# ProProject_board1_2023-08-19.net
KiCad netlist of a schematic drawn in EasyEDA Pro
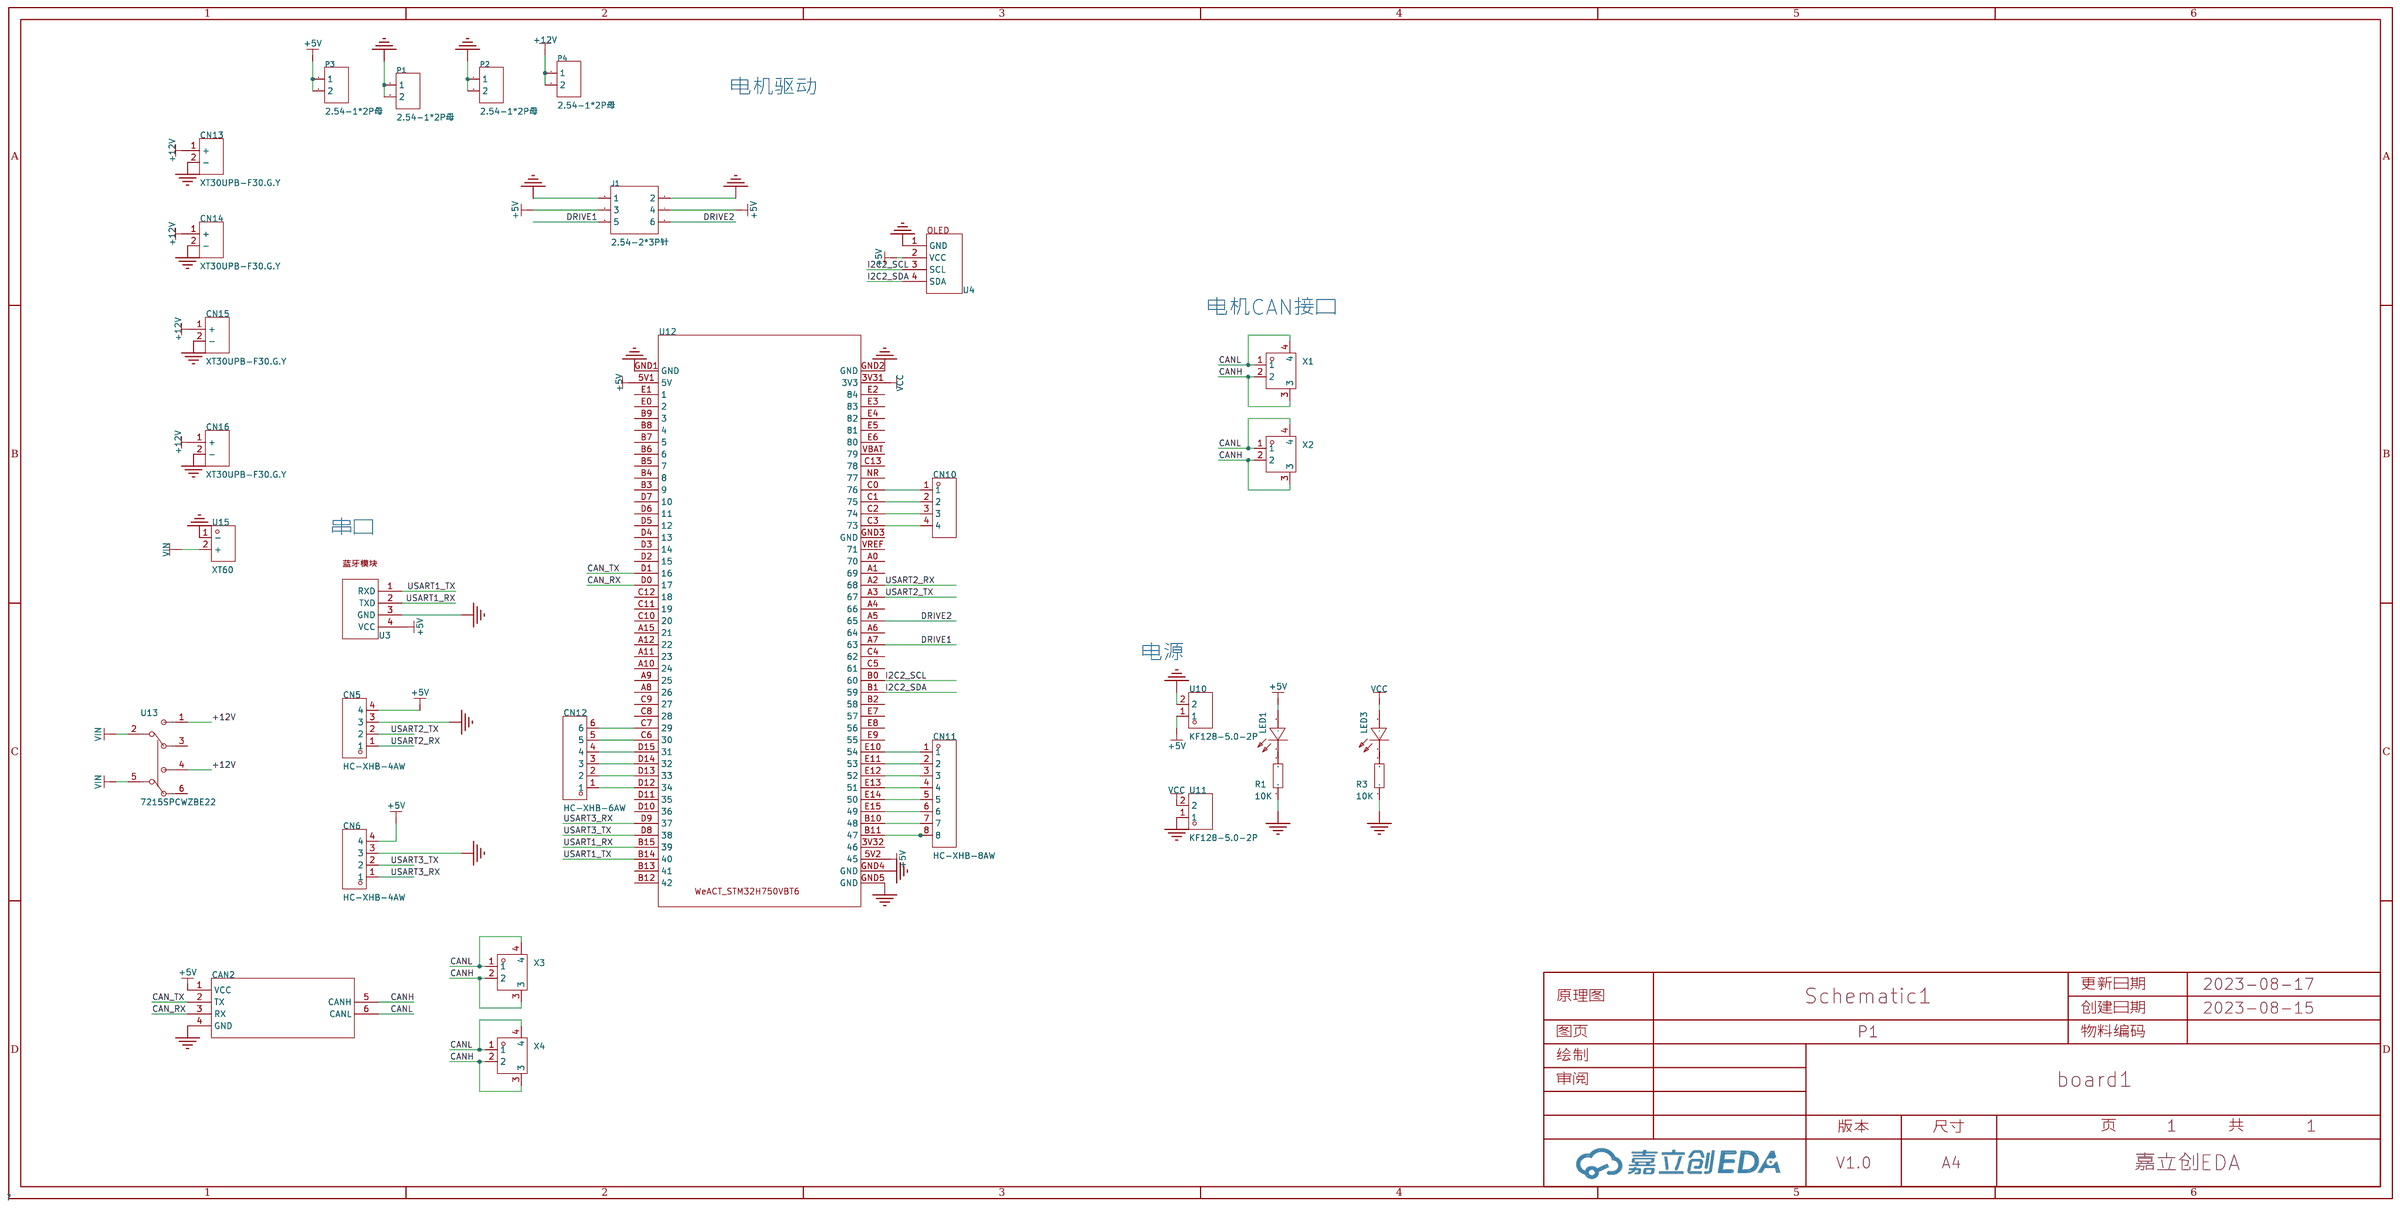
[diagram p0: schematic sheet]

(export (version "E")
  (design (tool "Eeschema 10.0.6"))
  (components
    (comp (ref "CAN2")
      (value "~")
      (footprint "easyedapro:CAN模块")
      (libsource (lib "easyedapro") (part "CAN模块"))
    )
    (comp (ref "CN5")
      (value "HC-XHB-4AW")
      (footprint "easyedapro:CONN-TH_4P-P2.5_HCTL_HC-XHB-4AW")
      (description "参考系列:-;间距:2.5mm;插针结构:1x4P;排数:1;每排PIN数:4;行距:-;公母:公型插针;安装方式:弯插;额定电流:3A;工作温度范围:-25°C~+85°C;")
      (fields (field (name "Manufacturer") "HCTL(华灿天禄)"))
      (libsource (lib "easyedapro") (part "HC-XHB-4AW"))
    )
    (comp (ref "CN6")
      (value "HC-XHB-4AW")
      (footprint "easyedapro:CONN-TH_4P-P2.5_HCTL_HC-XHB-4AW")
      (description "参考系列:-;间距:2.5mm;插针结构:1x4P;排数:1;每排PIN数:4;行距:-;公母:公型插针;安装方式:弯插;额定电流:3A;工作温度范围:-25°C~+85°C;")
      (fields (field (name "Manufacturer") "HCTL(华灿天禄)"))
      (libsource (lib "easyedapro") (part "HC-XHB-4AW"))
    )
    (comp (ref "CN10")
      (value "HC-XHB-4AW")
      (footprint "easyedapro:CONN-TH_4P-P2.5_HCTL_HC-XHB-4AW")
      (description "参考系列:-;间距:2.5mm;插针结构:1x4P;排数:1;每排PIN数:4;行距:-;公母:公型插针;安装方式:弯插;额定电流:3A;工作温度范围:-25°C~+85°C;")
      (fields (field (name "Manufacturer") "HCTL(华灿天禄)"))
      (libsource (lib "easyedapro") (part "HC-XHB-4AW"))
    )
    (comp (ref "CN11")
      (value "HC-XHB-8AW")
      (footprint "easyedapro:CONN-TH_HC-XHB-8AW")
      (description "参考系列:-;间距:2.5mm;插针结构:1x8P;排数:1;每排PIN数:8;行距:-;公母:公型插针;安装方式:弯插;额定电流:3A;工作温度范围:-25°C~+85°C;")
      (fields (field (name "Manufacturer") "HCTL(华灿天禄)"))
      (libsource (lib "easyedapro") (part "HC-XHB-8AW"))
    )
    (comp (ref "CN12")
      (value "HC-XHB-6AW")
      (footprint "easyedapro:CONN-TH_6P-P2.50_HCTL_HC-XHB-6AW")
      (description "参考系列:-;间距:2.5mm;插针结构:1x6P;排数:1;每排PIN数:6;行距:-;公母:公型插针;安装方式:弯插;额定电流:3A;工作温度范围:-25°C~+85°C;")
      (fields (field (name "Manufacturer") "HCTL(华灿天禄)"))
      (libsource (lib "easyedapro") (part "HC-XHB-6AW"))
    )
    (comp (ref "CN13")
      (value "XT30UPB-F30.G.Y")
      (footprint "easyedapro:CONN-TH_XT30UPB-F")
      (description "模型插头连接器")
      (fields (field (name "Manufacturer") "AMASS(艾迈斯)"))
      (libsource (lib "easyedapro") (part "XT30UPB-F"))
    )
    (comp (ref "CN14")
      (value "XT30UPB-F30.G.Y")
      (footprint "easyedapro:CONN-TH_XT30UPB-F")
      (description "模型插头连接器")
      (fields (field (name "Manufacturer") "AMASS(艾迈斯)"))
      (libsource (lib "easyedapro") (part "XT30UPB-F"))
    )
    (comp (ref "CN15")
      (value "XT30UPB-F30.G.Y")
      (footprint "easyedapro:CONN-TH_XT30UPB-F")
      (description "模型插头连接器")
      (fields (field (name "Manufacturer") "AMASS(艾迈斯)"))
      (libsource (lib "easyedapro") (part "XT30UPB-F"))
    )
    (comp (ref "CN16")
      (value "XT30UPB-F30.G.Y")
      (footprint "easyedapro:CONN-TH_XT30UPB-F")
      (description "模型插头连接器")
      (fields (field (name "Manufacturer") "AMASS(艾迈斯)"))
      (libsource (lib "easyedapro") (part "XT30UPB-F"))
    )
    (comp (ref "J1")
      (value "2.54-2*3P针")
      (footprint "easyedapro:HDR-TH_6P-P2.54-V-M-R2-C3-S2.54-1")
      (fields (field (name "Manufacturer") "BOOMELE(博穆精密)"))
      (libsource (lib "easyedapro") (part "Header-Male-2.54_2x3"))
    )
    (comp (ref "LED1")
      (value "NCD0805R1")
      (footprint "easyedapro:LED0805-RD_RED")
      (description "发光颜色:红灯;")
      (fields (field (name "Manufacturer") "国星光电"))
      (libsource (lib "easyedapro") (part "FC-2012HRK-620D"))
    )
    (comp (ref "LED3")
      (value "NCD0805R1")
      (footprint "easyedapro:LED0805-RD_RED")
      (description "发光颜色:红灯;")
      (fields (field (name "Manufacturer") "国星光电"))
      (libsource (lib "easyedapro") (part "FC-2012HRK-620D"))
    )
    (comp (ref "P1")
      (value "2.54-1*2P母")
      (footprint "easyedapro:HDR-TH_2P-P2.54-V-F")
      (description "排数:单排;总孔位数:2;间距:2.54mm;插孔结构:1x2P;行距:-;安装类型:直插;塑高:-;触头材质:-;触头镀层:-;")
      (fields (field (name "Manufacturer") "BOOMELE(博穆精密)"))
      (libsource (lib "easyedapro") (part "Header-Female-2.54_1x2"))
    )
    (comp (ref "P2")
      (value "2.54-1*2P母")
      (footprint "easyedapro:HDR-TH_2P-P2.54-V-F")
      (description "排数:单排;总孔位数:2;间距:2.54mm;插孔结构:1x2P;行距:-;安装类型:直插;塑高:-;触头材质:-;触头镀层:-;")
      (fields (field (name "Manufacturer") "BOOMELE(博穆精密)"))
      (libsource (lib "easyedapro") (part "Header-Female-2.54_1x2"))
    )
    (comp (ref "P3")
      (value "2.54-1*2P母")
      (footprint "easyedapro:HDR-TH_2P-P2.54-V-F")
      (description "排数:单排;总孔位数:2;间距:2.54mm;插孔结构:1x2P;行距:-;安装类型:直插;塑高:-;触头材质:-;触头镀层:-;")
      (fields (field (name "Manufacturer") "BOOMELE(博穆精密)"))
      (libsource (lib "easyedapro") (part "Header-Female-2.54_1x2"))
    )
    (comp (ref "P4")
      (value "2.54-1*2P母")
      (footprint "easyedapro:HDR-TH_2P-P2.54-V-F")
      (description "排数:单排;总孔位数:2;间距:2.54mm;插孔结构:1x2P;行距:-;安装类型:直插;塑高:-;触头材质:-;触头镀层:-;")
      (fields (field (name "Manufacturer") "BOOMELE(博穆精密)"))
      (libsource (lib "easyedapro") (part "Header-Female-2.54_1x2"))
    )
    (comp (ref "R1") (value "10K") (footprint "easyedapro:R0603") (libsource (lib "easyedapro") (part "电阻")))
    (comp (ref "R3") (value "10K") (footprint "easyedapro:R0603") (libsource (lib "easyedapro") (part "电阻")))
    (comp (ref "U3") (value "~") (footprint "easyedapro:蓝牙模块") (libsource (lib "easyedapro") (part "蓝牙模块")))
    (comp (ref "U4") (value "~") (footprint "easyedapro:OLED") (libsource (lib "easyedapro") (part "OLED")))
    (comp (ref "U10")
      (value "KF128-5.0-2P")
      (footprint "easyedapro:CONN-TH_P5.00_KF128-5.0-2P")
      (fields (field (name "Manufacturer") "KEFA(科发)"))
      (libsource (lib "easyedapro") (part "KF128-5.0-2P"))
    )
    (comp (ref "U11")
      (value "KF128-5.0-2P")
      (footprint "easyedapro:CONN-TH_P5.00_KF128-5.0-2P")
      (fields (field (name "Manufacturer") "KEFA(科发)"))
      (libsource (lib "easyedapro") (part "KF128-5.0-2P"))
    )
    (comp (ref "U12")
      (value "~")
      (footprint "easyedapro:WeAct_STM32H750VBT6核心板")
      (libsource (lib "easyedapro") (part "STM32H750VBT6"))
    )
    (comp (ref "U13")
      (value "7215SPCWZBE22")
      (footprint "easyedapro:SW-TH_6P-L12.7-W11.4-P4.70-LS4.8")
      (fields (field (name "Manufacturer") "CK"))
      (libsource (lib "easyedapro") (part "7215SPCWZBE22"))
    )
    (comp (ref "U15")
      (value "XT60")
      (footprint "easyedapro:CONN-TH_XT60")
      (description "模型锂电连接器 XT60-M")
      (fields (field (name "Manufacturer") "AMASS(艾迈斯)"))
      (libsource (lib "easyedapro") (part "XT60"))
    )
    (comp (ref "X1")
      (value "GH125-S02DCA-00")
      (footprint "easyedapro:CONN-SMD_2P-P1.25_JUSHUO_GH125-S02DCA-00")
      (description "参考系列:-;间距:1.25mm;插针结构:1x2P;排数:1;每排PIN数:2;行距:-;公母:公型插针;安装方式:卧贴;额定电流:1A;工作温度范围:-25°C~+85°C;")
      (fields (field (name "Manufacturer") "JS(钜硕电子)"))
      (libsource (lib "easyedapro") (part "GH125-S02DCA-00"))
    )
    (comp (ref "X2")
      (value "GH125-S02DCA-00")
      (footprint "easyedapro:CONN-SMD_2P-P1.25_JUSHUO_GH125-S02DCA-00")
      (description "参考系列:-;间距:1.25mm;插针结构:1x2P;排数:1;每排PIN数:2;行距:-;公母:公型插针;安装方式:卧贴;额定电流:1A;工作温度范围:-25°C~+85°C;")
      (fields (field (name "Manufacturer") "JS(钜硕电子)"))
      (libsource (lib "easyedapro") (part "GH125-S02DCA-00"))
    )
    (comp (ref "X3")
      (value "GH125-S02DCA-00")
      (footprint "easyedapro:CONN-SMD_2P-P1.25_JUSHUO_GH125-S02DCA-00")
      (description "参考系列:-;间距:1.25mm;插针结构:1x2P;排数:1;每排PIN数:2;行距:-;公母:公型插针;安装方式:卧贴;额定电流:1A;工作温度范围:-25°C~+85°C;")
      (fields (field (name "Manufacturer") "JS(钜硕电子)"))
      (libsource (lib "easyedapro") (part "GH125-S02DCA-00"))
    )
    (comp (ref "X4")
      (value "GH125-S02DCA-00")
      (footprint "easyedapro:CONN-SMD_2P-P1.25_JUSHUO_GH125-S02DCA-00")
      (description "参考系列:-;间距:1.25mm;插针结构:1x2P;排数:1;每排PIN数:2;行距:-;公母:公型插针;安装方式:卧贴;额定电流:1A;工作温度范围:-25°C~+85°C;")
      (fields (field (name "Manufacturer") "JS(钜硕电子)"))
      (libsource (lib "easyedapro") (part "GH125-S02DCA-00"))
    )
  )
  (nets
    (net (code "1") (name "+5V") (class "Default")
      (node (ref "CAN2") (pin "1") (pinfunction "VCC_1") (pintype "input"))
      (node (ref "CN5") (pin "4") (pinfunction "4_4") (pintype "input"))
      (node (ref "CN6") (pin "4") (pinfunction "4_4") (pintype "input"))
      (node (ref "J1") (pin "3") (pinfunction "3_3") (pintype "input"))
      (node (ref "J1") (pin "4") (pinfunction "4_4") (pintype "input"))
      (node (ref "LED1") (pin "2") (pinfunction "+_2") (pintype "input"))
      (node (ref "P3") (pin "1") (pinfunction "1_1") (pintype "input"))
      (node (ref "P3") (pin "2") (pinfunction "2_2") (pintype "input"))
      (node (ref "U10") (pin "1") (pinfunction "1_1") (pintype "input"))
      (node (ref "U12") (pin "5V1") (pinfunction "5V_5V1") (pintype "input"))
      (node (ref "U12") (pin "5V2") (pinfunction "45_5V2") (pintype "input"))
      (node (ref "U3") (pin "4") (pinfunction "VCC_4") (pintype "input"))
      (node (ref "U4") (pin "2") (pinfunction "VCC_2") (pintype "input"))
    )
    (net (code "2") (name "+12V") (class "Default")
      (node (ref "CN13") (pin "1") (pinfunction "+_1") (pintype "input"))
      (node (ref "CN14") (pin "1") (pinfunction "+_1") (pintype "input"))
      (node (ref "CN15") (pin "1") (pinfunction "+_1") (pintype "input"))
      (node (ref "CN16") (pin "1") (pinfunction "+_1") (pintype "input"))
      (node (ref "P4") (pin "1") (pinfunction "1_1") (pintype "input"))
      (node (ref "P4") (pin "2") (pinfunction "2_2") (pintype "input"))
      (node (ref "U13") (pin "1") (pinfunction "1_1") (pintype "input"))
      (node (ref "U13") (pin "4") (pinfunction "4_4") (pintype "input"))
    )
    (net (code "3") (name "/CANH") (class "Default")
      (node (ref "CAN2") (pin "5") (pinfunction "CANH_5") (pintype "input"))
      (node (ref "X1") (pin "2") (pinfunction "2_2") (pintype "input"))
      (node (ref "X1") (pin "3") (pinfunction "3_3") (pintype "input"))
      (node (ref "X2") (pin "2") (pinfunction "2_2") (pintype "input"))
      (node (ref "X2") (pin "3") (pinfunction "3_3") (pintype "input"))
      (node (ref "X3") (pin "2") (pinfunction "2_2") (pintype "input"))
      (node (ref "X3") (pin "3") (pinfunction "3_3") (pintype "input"))
      (node (ref "X4") (pin "2") (pinfunction "2_2") (pintype "input"))
      (node (ref "X4") (pin "3") (pinfunction "3_3") (pintype "input"))
    )
    (net (code "4") (name "/CANL") (class "Default")
      (node (ref "CAN2") (pin "6") (pinfunction "CANL_6") (pintype "input"))
      (node (ref "X1") (pin "1") (pinfunction "1_1") (pintype "input"))
      (node (ref "X1") (pin "4") (pinfunction "4_4") (pintype "input"))
      (node (ref "X2") (pin "1") (pinfunction "1_1") (pintype "input"))
      (node (ref "X2") (pin "4") (pinfunction "4_4") (pintype "input"))
      (node (ref "X3") (pin "1") (pinfunction "1_1") (pintype "input"))
      (node (ref "X3") (pin "4") (pinfunction "4_4") (pintype "input"))
      (node (ref "X4") (pin "1") (pinfunction "1_1") (pintype "input"))
      (node (ref "X4") (pin "4") (pinfunction "4_4") (pintype "input"))
    )
    (net (code "5") (name "/CAN_RX") (class "Default")
      (node (ref "CAN2") (pin "3") (pinfunction "RX_3") (pintype "input"))
      (node (ref "U12") (pin "D0") (pinfunction "17_D0") (pintype "input"))
    )
    (net (code "6") (name "/CAN_TX") (class "Default")
      (node (ref "CAN2") (pin "2") (pinfunction "TX_2") (pintype "input"))
      (node (ref "U12") (pin "D1") (pinfunction "16_D1") (pintype "input"))
    )
    (net (code "7") (name "/DRIVE1") (class "Default")
      (node (ref "J1") (pin "5") (pinfunction "5_5") (pintype "input"))
      (node (ref "U12") (pin "A7") (pinfunction "63_A7") (pintype "input"))
    )
    (net (code "8") (name "/DRIVE2") (class "Default")
      (node (ref "J1") (pin "6") (pinfunction "6_6") (pintype "input"))
      (node (ref "U12") (pin "A5") (pinfunction "65_A5") (pintype "input"))
    )
    (net (code "9") (name "/I2C2_SCL") (class "Default")
      (node (ref "U12") (pin "B0") (pinfunction "60_B0") (pintype "input"))
      (node (ref "U4") (pin "3") (pinfunction "SCL_3") (pintype "input"))
    )
    (net (code "10") (name "/I2C2_SDA") (class "Default")
      (node (ref "U12") (pin "B1") (pinfunction "59_B1") (pintype "input"))
      (node (ref "U4") (pin "4") (pinfunction "SDA_4") (pintype "input"))
    )
    (net (code "11") (name "/USART1_RX") (class "Default")
      (node (ref "U12") (pin "B15") (pinfunction "39_B15") (pintype "input"))
      (node (ref "U3") (pin "2") (pinfunction "TXD_2") (pintype "input"))
    )
    (net (code "12") (name "/USART1_TX") (class "Default")
      (node (ref "U12") (pin "B14") (pinfunction "40_B14") (pintype "input"))
      (node (ref "U3") (pin "1") (pinfunction "RXD_1") (pintype "input"))
    )
    (net (code "13") (name "/USART2_RX") (class "Default")
      (node (ref "CN5") (pin "1") (pinfunction "1_1") (pintype "input"))
      (node (ref "U12") (pin "A2") (pinfunction "68_A2") (pintype "input"))
    )
    (net (code "14") (name "/USART2_TX") (class "Default")
      (node (ref "CN5") (pin "2") (pinfunction "2_2") (pintype "input"))
      (node (ref "U12") (pin "A3") (pinfunction "67_A3") (pintype "input"))
    )
    (net (code "15") (name "/USART3_RX") (class "Default")
      (node (ref "CN6") (pin "1") (pinfunction "1_1") (pintype "input"))
      (node (ref "U12") (pin "D9") (pinfunction "37_D9") (pintype "input"))
    )
    (net (code "16") (name "/USART3_TX") (class "Default")
      (node (ref "CN6") (pin "2") (pinfunction "2_2") (pintype "input"))
      (node (ref "U12") (pin "D8") (pinfunction "38_D8") (pintype "input"))
    )
    (net (code "17") (name "GND") (class "Default")
      (node (ref "CAN2") (pin "4") (pinfunction "GND_4") (pintype "input"))
      (node (ref "CN13") (pin "2") (pinfunction "-_2") (pintype "input"))
      (node (ref "CN14") (pin "2") (pinfunction "-_2") (pintype "input"))
      (node (ref "CN15") (pin "2") (pinfunction "-_2") (pintype "input"))
      (node (ref "CN16") (pin "2") (pinfunction "-_2") (pintype "input"))
      (node (ref "CN5") (pin "3") (pinfunction "3_3") (pintype "input"))
      (node (ref "CN6") (pin "3") (pinfunction "3_3") (pintype "input"))
      (node (ref "J1") (pin "1") (pinfunction "1_1") (pintype "input"))
      (node (ref "J1") (pin "2") (pinfunction "2_2") (pintype "input"))
      (node (ref "P1") (pin "1") (pinfunction "1_1") (pintype "input"))
      (node (ref "P1") (pin "2") (pinfunction "2_2") (pintype "input"))
      (node (ref "P2") (pin "1") (pinfunction "1_1") (pintype "input"))
      (node (ref "P2") (pin "2") (pinfunction "2_2") (pintype "input"))
      (node (ref "R1") (pin "1") (pinfunction "1_1") (pintype "input"))
      (node (ref "R3") (pin "1") (pinfunction "1_1") (pintype "input"))
      (node (ref "U10") (pin "2") (pinfunction "2_2") (pintype "input"))
      (node (ref "U11") (pin "1") (pinfunction "1_1") (pintype "input"))
      (node (ref "U12") (pin "GND1") (pinfunction "GND_GND1") (pintype "input"))
      (node (ref "U12") (pin "GND2") (pinfunction "GND_GND2") (pintype "input"))
      (node (ref "U12") (pin "GND4") (pinfunction "GND_GND4") (pintype "input"))
      (node (ref "U12") (pin "GND5") (pinfunction "GND_GND5") (pintype "input"))
      (node (ref "U15") (pin "1") (pinfunction "-_1") (pintype "input"))
      (node (ref "U3") (pin "3") (pinfunction "GND_3") (pintype "input"))
      (node (ref "U4") (pin "1") (pinfunction "GND_1") (pintype "input"))
    )
    (net (code "18") (name "Net-(LED1--)") (class "Default")
      (node (ref "LED1") (pin "1") (pinfunction "-_1") (pintype "input"))
      (node (ref "R1") (pin "2") (pinfunction "2_2") (pintype "input"))
    )
    (net (code "19") (name "Net-(LED3--)") (class "Default")
      (node (ref "LED3") (pin "1") (pinfunction "-_1") (pintype "input"))
      (node (ref "R3") (pin "2") (pinfunction "2_2") (pintype "input"))
    )
    (net (code "20") (name "Net-(U12-29)") (class "Default")
      (node (ref "CN12") (pin "6") (pinfunction "6_6") (pintype "input"))
      (node (ref "U12") (pin "C7") (pinfunction "29_C7") (pintype "input"))
    )
    (net (code "21") (name "Net-(U12-30)") (class "Default")
      (node (ref "CN12") (pin "5") (pinfunction "5_5") (pintype "input"))
      (node (ref "U12") (pin "C6") (pinfunction "30_C6") (pintype "input"))
    )
    (net (code "22") (name "Net-(U12-31)") (class "Default")
      (node (ref "CN12") (pin "4") (pinfunction "4_4") (pintype "input"))
      (node (ref "U12") (pin "D15") (pinfunction "31_D15") (pintype "input"))
    )
    (net (code "23") (name "Net-(U12-32)") (class "Default")
      (node (ref "CN12") (pin "3") (pinfunction "3_3") (pintype "input"))
      (node (ref "U12") (pin "D14") (pinfunction "32_D14") (pintype "input"))
    )
    (net (code "24") (name "Net-(U12-33)") (class "Default")
      (node (ref "CN12") (pin "2") (pinfunction "2_2") (pintype "input"))
      (node (ref "U12") (pin "D13") (pinfunction "33_D13") (pintype "input"))
    )
    (net (code "25") (name "Net-(U12-34)") (class "Default")
      (node (ref "CN12") (pin "1") (pinfunction "1_1") (pintype "input"))
      (node (ref "U12") (pin "D12") (pinfunction "34_D12") (pintype "input"))
    )
    (net (code "26") (name "Net-(U12-47)") (class "Default")
      (node (ref "CN11") (pin "8") (pinfunction "8_8") (pintype "input"))
      (node (ref "U12") (pin "B11") (pinfunction "47_B11") (pintype "input"))
    )
    (net (code "27") (name "Net-(U12-48)") (class "Default")
      (node (ref "CN11") (pin "7") (pinfunction "7_7") (pintype "input"))
      (node (ref "U12") (pin "B10") (pinfunction "48_B10") (pintype "input"))
    )
    (net (code "28") (name "Net-(U12-49)") (class "Default")
      (node (ref "CN11") (pin "6") (pinfunction "6_6") (pintype "input"))
      (node (ref "U12") (pin "E15") (pinfunction "49_E15") (pintype "input"))
    )
    (net (code "29") (name "Net-(U12-50)") (class "Default")
      (node (ref "CN11") (pin "5") (pinfunction "5_5") (pintype "input"))
      (node (ref "U12") (pin "E14") (pinfunction "50_E14") (pintype "input"))
    )
    (net (code "30") (name "Net-(U12-51)") (class "Default")
      (node (ref "CN11") (pin "4") (pinfunction "4_4") (pintype "input"))
      (node (ref "U12") (pin "E13") (pinfunction "51_E13") (pintype "input"))
    )
    (net (code "31") (name "Net-(U12-52)") (class "Default")
      (node (ref "CN11") (pin "3") (pinfunction "3_3") (pintype "input"))
      (node (ref "U12") (pin "E12") (pinfunction "52_E12") (pintype "input"))
    )
    (net (code "32") (name "Net-(U12-53)") (class "Default")
      (node (ref "CN11") (pin "2") (pinfunction "2_2") (pintype "input"))
      (node (ref "U12") (pin "E11") (pinfunction "53_E11") (pintype "input"))
    )
    (net (code "33") (name "Net-(U12-54)") (class "Default")
      (node (ref "CN11") (pin "1") (pinfunction "1_1") (pintype "input"))
      (node (ref "U12") (pin "E10") (pinfunction "54_E10") (pintype "input"))
    )
    (net (code "34") (name "Net-(U12-73)") (class "Default")
      (node (ref "CN10") (pin "4") (pinfunction "4_4") (pintype "input"))
      (node (ref "U12") (pin "C3") (pinfunction "73_C3") (pintype "input"))
    )
    (net (code "35") (name "Net-(U12-74)") (class "Default")
      (node (ref "CN10") (pin "3") (pinfunction "3_3") (pintype "input"))
      (node (ref "U12") (pin "C2") (pinfunction "74_C2") (pintype "input"))
    )
    (net (code "36") (name "Net-(U12-75)") (class "Default")
      (node (ref "CN10") (pin "2") (pinfunction "2_2") (pintype "input"))
      (node (ref "U12") (pin "C1") (pinfunction "75_C1") (pintype "input"))
    )
    (net (code "37") (name "Net-(U12-76)") (class "Default")
      (node (ref "CN10") (pin "1") (pinfunction "1_1") (pintype "input"))
      (node (ref "U12") (pin "C0") (pinfunction "76_C0") (pintype "input"))
    )
    (net (code "38") (name "VCC") (class "Default")
      (node (ref "LED3") (pin "2") (pinfunction "+_2") (pintype "input"))
      (node (ref "U11") (pin "2") (pinfunction "2_2") (pintype "input"))
      (node (ref "U12") (pin "3V31") (pinfunction "3V3_3V31") (pintype "input"))
    )
    (net (code "39") (name "VIN") (class "Default")
      (node (ref "U13") (pin "2") (pinfunction "2_2") (pintype "input"))
      (node (ref "U13") (pin "5") (pinfunction "5_5") (pintype "input"))
      (node (ref "U15") (pin "2") (pinfunction "+_2") (pintype "input"))
    )
    (net (code "40") (name "unconnected-(U12-1-PadE1)") (class "Default")
      (node (ref "U12") (pin "E1") (pinfunction "1_E1") (pintype "input"))
    )
    (net (code "41") (name "unconnected-(U12-2-PadE0)") (class "Default")
      (node (ref "U12") (pin "E0") (pinfunction "2_E0") (pintype "input"))
    )
    (net (code "42") (name "unconnected-(U12-3-PadB9)") (class "Default")
      (node (ref "U12") (pin "B9") (pinfunction "3_B9") (pintype "input"))
    )
    (net (code "43") (name "unconnected-(U12-4-PadB8)") (class "Default")
      (node (ref "U12") (pin "B8") (pinfunction "4_B8") (pintype "input"))
    )
    (net (code "44") (name "unconnected-(U12-5-PadB7)") (class "Default")
      (node (ref "U12") (pin "B7") (pinfunction "5_B7") (pintype "input"))
    )
    (net (code "45") (name "unconnected-(U12-6-PadB6)") (class "Default")
      (node (ref "U12") (pin "B6") (pinfunction "6_B6") (pintype "input"))
    )
    (net (code "46") (name "unconnected-(U12-7-PadB5)") (class "Default")
      (node (ref "U12") (pin "B5") (pinfunction "7_B5") (pintype "input"))
    )
    (net (code "47") (name "unconnected-(U12-8-PadB4)") (class "Default")
      (node (ref "U12") (pin "B4") (pinfunction "8_B4") (pintype "input"))
    )
    (net (code "48") (name "unconnected-(U12-9-PadB3)") (class "Default")
      (node (ref "U12") (pin "B3") (pinfunction "9_B3") (pintype "input"))
    )
    (net (code "49") (name "unconnected-(U12-10-PadD7)") (class "Default")
      (node (ref "U12") (pin "D7") (pinfunction "10_D7") (pintype "input"))
    )
    (net (code "50") (name "unconnected-(U12-11-PadD6)") (class "Default")
      (node (ref "U12") (pin "D6") (pinfunction "11_D6") (pintype "input"))
    )
    (net (code "51") (name "unconnected-(U12-12-PadD5)") (class "Default")
      (node (ref "U12") (pin "D5") (pinfunction "12_D5") (pintype "input"))
    )
    (net (code "52") (name "unconnected-(U12-13-PadD4)") (class "Default")
      (node (ref "U12") (pin "D4") (pinfunction "13_D4") (pintype "input"))
    )
    (net (code "53") (name "unconnected-(U12-14-PadD3)") (class "Default")
      (node (ref "U12") (pin "D3") (pinfunction "14_D3") (pintype "input"))
    )
    (net (code "54") (name "unconnected-(U12-15-PadD2)") (class "Default")
      (node (ref "U12") (pin "D2") (pinfunction "15_D2") (pintype "input"))
    )
    (net (code "55") (name "unconnected-(U12-18-PadC12)") (class "Default")
      (node (ref "U12") (pin "C12") (pinfunction "18_C12") (pintype "input"))
    )
    (net (code "56") (name "unconnected-(U12-19-PadC11)") (class "Default")
      (node (ref "U12") (pin "C11") (pinfunction "19_C11") (pintype "input"))
    )
    (net (code "57") (name "unconnected-(U12-20-PadC10)") (class "Default")
      (node (ref "U12") (pin "C10") (pinfunction "20_C10") (pintype "input"))
    )
    (net (code "58") (name "unconnected-(U12-21-PadA15)") (class "Default")
      (node (ref "U12") (pin "A15") (pinfunction "21_A15") (pintype "input"))
    )
    (net (code "59") (name "unconnected-(U12-22-PadA12)") (class "Default")
      (node (ref "U12") (pin "A12") (pinfunction "22_A12") (pintype "input"))
    )
    (net (code "60") (name "unconnected-(U12-23-PadA11)") (class "Default")
      (node (ref "U12") (pin "A11") (pinfunction "23_A11") (pintype "input"))
    )
    (net (code "61") (name "unconnected-(U12-24-PadA10)") (class "Default")
      (node (ref "U12") (pin "A10") (pinfunction "24_A10") (pintype "input"))
    )
    (net (code "62") (name "unconnected-(U12-25-PadA9)") (class "Default")
      (node (ref "U12") (pin "A9") (pinfunction "25_A9") (pintype "input"))
    )
    (net (code "63") (name "unconnected-(U12-26-PadA8)") (class "Default")
      (node (ref "U12") (pin "A8") (pinfunction "26_A8") (pintype "input"))
    )
    (net (code "64") (name "unconnected-(U12-27-PadC9)") (class "Default")
      (node (ref "U12") (pin "C9") (pinfunction "27_C9") (pintype "input"))
    )
    (net (code "65") (name "unconnected-(U12-28-PadC8)") (class "Default")
      (node (ref "U12") (pin "C8") (pinfunction "28_C8") (pintype "input"))
    )
    (net (code "66") (name "unconnected-(U12-35-PadD11)") (class "Default")
      (node (ref "U12") (pin "D11") (pinfunction "35_D11") (pintype "input"))
    )
    (net (code "67") (name "unconnected-(U12-36-PadD10)") (class "Default")
      (node (ref "U12") (pin "D10") (pinfunction "36_D10") (pintype "input"))
    )
    (net (code "68") (name "unconnected-(U12-41-PadB13)") (class "Default")
      (node (ref "U12") (pin "B13") (pinfunction "41_B13") (pintype "input"))
    )
    (net (code "69") (name "unconnected-(U12-42-PadB12)") (class "Default")
      (node (ref "U12") (pin "B12") (pinfunction "42_B12") (pintype "input"))
    )
    (net (code "70") (name "unconnected-(U12-46-Pad3V32)") (class "Default")
      (node (ref "U12") (pin "3V32") (pinfunction "46_3V32") (pintype "input"))
    )
    (net (code "71") (name "unconnected-(U12-55-PadE9)") (class "Default")
      (node (ref "U12") (pin "E9") (pinfunction "55_E9") (pintype "input"))
    )
    (net (code "72") (name "unconnected-(U12-56-PadE8)") (class "Default")
      (node (ref "U12") (pin "E8") (pinfunction "56_E8") (pintype "input"))
    )
    (net (code "73") (name "unconnected-(U12-57-PadE7)") (class "Default")
      (node (ref "U12") (pin "E7") (pinfunction "57_E7") (pintype "input"))
    )
    (net (code "74") (name "unconnected-(U12-58-PadB2)") (class "Default")
      (node (ref "U12") (pin "B2") (pinfunction "58_B2") (pintype "input"))
    )
    (net (code "75") (name "unconnected-(U12-61-PadC5)") (class "Default")
      (node (ref "U12") (pin "C5") (pinfunction "61_C5") (pintype "input"))
    )
    (net (code "76") (name "unconnected-(U12-62-PadC4)") (class "Default")
      (node (ref "U12") (pin "C4") (pinfunction "62_C4") (pintype "input"))
    )
    (net (code "77") (name "unconnected-(U12-64-PadA6)") (class "Default")
      (node (ref "U12") (pin "A6") (pinfunction "64_A6") (pintype "input"))
    )
    (net (code "78") (name "unconnected-(U12-66-PadA4)") (class "Default")
      (node (ref "U12") (pin "A4") (pinfunction "66_A4") (pintype "input"))
    )
    (net (code "79") (name "unconnected-(U12-69-PadA1)") (class "Default")
      (node (ref "U12") (pin "A1") (pinfunction "69_A1") (pintype "input"))
    )
    (net (code "80") (name "unconnected-(U12-70-PadA0)") (class "Default")
      (node (ref "U12") (pin "A0") (pinfunction "70_A0") (pintype "input"))
    )
    (net (code "81") (name "unconnected-(U12-71-PadVREF)") (class "Default")
      (node (ref "U12") (pin "VREF") (pinfunction "71_VREF") (pintype "input"))
    )
    (net (code "82") (name "unconnected-(U12-77-PadNR)") (class "Default")
      (node (ref "U12") (pin "NR") (pinfunction "77_NR") (pintype "input"))
    )
    (net (code "83") (name "unconnected-(U12-78-PadC13)") (class "Default")
      (node (ref "U12") (pin "C13") (pinfunction "78_C13") (pintype "input"))
    )
    (net (code "84") (name "unconnected-(U12-79-PadVBAT)") (class "Default")
      (node (ref "U12") (pin "VBAT") (pinfunction "79_VBAT") (pintype "input"))
    )
    (net (code "85") (name "unconnected-(U12-80-PadE6)") (class "Default")
      (node (ref "U12") (pin "E6") (pinfunction "80_E6") (pintype "input"))
    )
    (net (code "86") (name "unconnected-(U12-81-PadE5)") (class "Default")
      (node (ref "U12") (pin "E5") (pinfunction "81_E5") (pintype "input"))
    )
    (net (code "87") (name "unconnected-(U12-82-PadE4)") (class "Default")
      (node (ref "U12") (pin "E4") (pinfunction "82_E4") (pintype "input"))
    )
    (net (code "88") (name "unconnected-(U12-83-PadE3)") (class "Default")
      (node (ref "U12") (pin "E3") (pinfunction "83_E3") (pintype "input"))
    )
    (net (code "89") (name "unconnected-(U12-84-PadE2)") (class "Default")
      (node (ref "U12") (pin "E2") (pinfunction "84_E2") (pintype "input"))
    )
    (net (code "90") (name "unconnected-(U12-GND-PadGND3)") (class "Default")
      (node (ref "U12") (pin "GND3") (pinfunction "GND_GND3") (pintype "input"))
    )
    (net (code "91") (name "unconnected-(U13-Pad3)") (class "Default")
      (node (ref "U13") (pin "3") (pinfunction "3_3") (pintype "input"))
    )
    (net (code "92") (name "unconnected-(U13-Pad6)") (class "Default")
      (node (ref "U13") (pin "6") (pinfunction "6_6") (pintype "input"))
    )
  )
)
